# Charging_dock_2_1.net
KiCad netlist of a schematic drawn in EAGLE
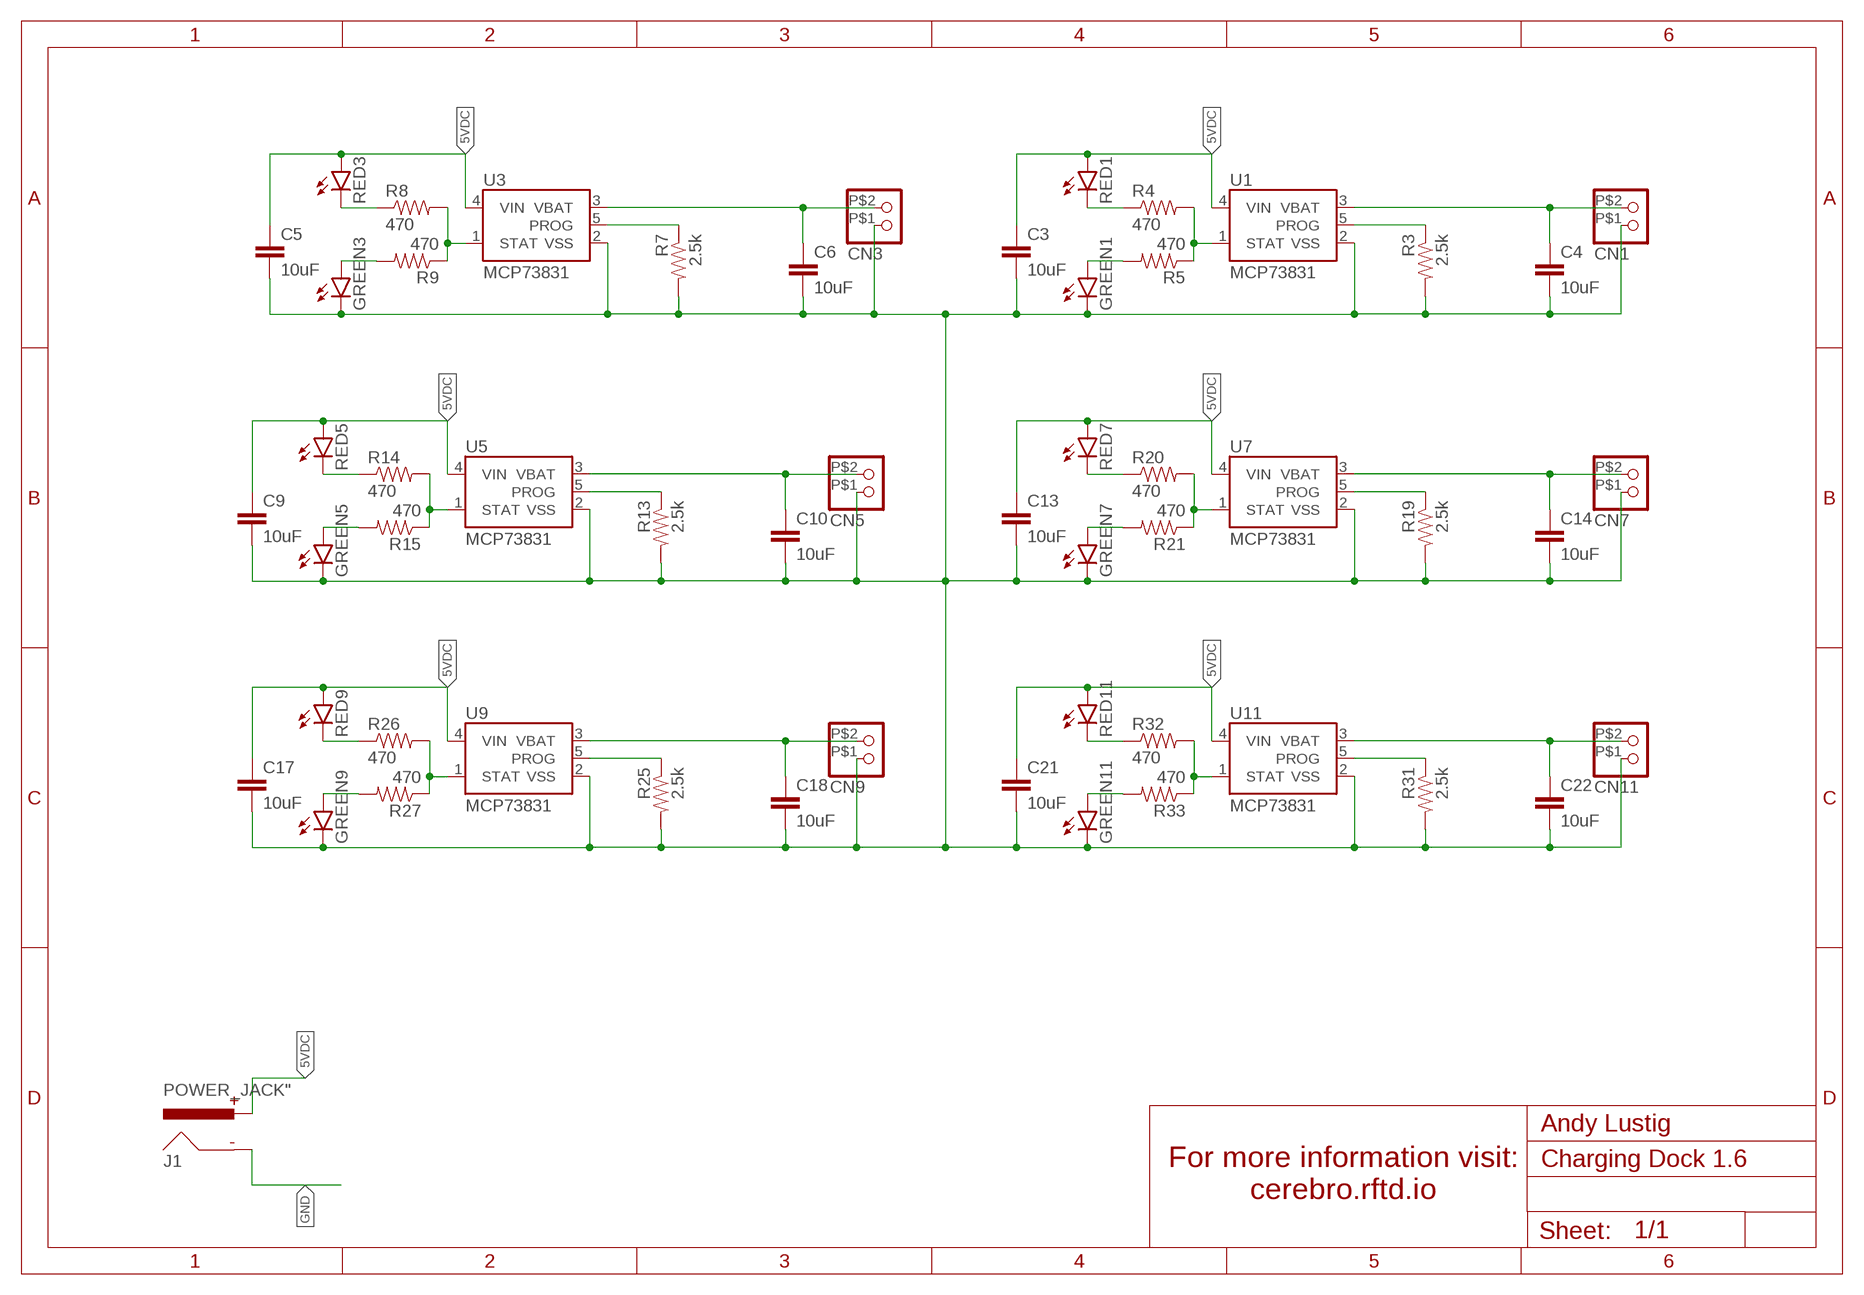
[diagram p0: schematic, sheet 1]

(export (version "E")
  (design (tool "Eeschema 10.0.6"))
  (components
    (comp (ref "C3")
      (value "10uF")
      (footprint "eagle-import:0805")
      (libsource (lib "eagle-import") (part "10UF-0805-10V-10%"))
    )
    (comp (ref "C4")
      (value "10uF")
      (footprint "eagle-import:0805")
      (libsource (lib "eagle-import") (part "10UF-0805-10V-10%"))
    )
    (comp (ref "C5")
      (value "10uF")
      (footprint "eagle-import:0805")
      (libsource (lib "eagle-import") (part "10UF-0805-10V-10%"))
    )
    (comp (ref "C6")
      (value "10uF")
      (footprint "eagle-import:0805")
      (libsource (lib "eagle-import") (part "10UF-0805-10V-10%"))
    )
    (comp (ref "C9")
      (value "10uF")
      (footprint "eagle-import:0805")
      (libsource (lib "eagle-import") (part "10UF-0805-10V-10%"))
    )
    (comp (ref "C10")
      (value "10uF")
      (footprint "eagle-import:0805")
      (libsource (lib "eagle-import") (part "10UF-0805-10V-10%"))
    )
    (comp (ref "C13")
      (value "10uF")
      (footprint "eagle-import:0805")
      (libsource (lib "eagle-import") (part "10UF-0805-10V-10%"))
    )
    (comp (ref "C14")
      (value "10uF")
      (footprint "eagle-import:0805")
      (libsource (lib "eagle-import") (part "10UF-0805-10V-10%"))
    )
    (comp (ref "C17")
      (value "10uF")
      (footprint "eagle-import:0805")
      (libsource (lib "eagle-import") (part "10UF-0805-10V-10%"))
    )
    (comp (ref "C18")
      (value "10uF")
      (footprint "eagle-import:0805")
      (libsource (lib "eagle-import") (part "10UF-0805-10V-10%"))
    )
    (comp (ref "C21")
      (value "10uF")
      (footprint "eagle-import:0805")
      (libsource (lib "eagle-import") (part "10UF-0805-10V-10%"))
    )
    (comp (ref "C22")
      (value "10uF")
      (footprint "eagle-import:0805")
      (libsource (lib "eagle-import") (part "10UF-0805-10V-10%"))
    )
    (comp (ref "CN1")
      (value "JST_2PINMICRO")
      (footprint "eagle-import:MICRO_LOCK_2PIN")
      (libsource (lib "eagle-import") (part "JST_2PINMICRO"))
    )
    (comp (ref "CN3")
      (value "JST_2PINMICRO")
      (footprint "eagle-import:MICRO_LOCK_2PIN")
      (libsource (lib "eagle-import") (part "JST_2PINMICRO"))
    )
    (comp (ref "CN5")
      (value "JST_2PINMICRO")
      (footprint "eagle-import:MICRO_LOCK_2PIN")
      (libsource (lib "eagle-import") (part "JST_2PINMICRO"))
    )
    (comp (ref "CN7")
      (value "JST_2PINMICRO")
      (footprint "eagle-import:MICRO_LOCK_2PIN")
      (libsource (lib "eagle-import") (part "JST_2PINMICRO"))
    )
    (comp (ref "CN9")
      (value "JST_2PINMICRO")
      (footprint "eagle-import:MICRO_LOCK_2PIN")
      (libsource (lib "eagle-import") (part "JST_2PINMICRO"))
    )
    (comp (ref "CN11")
      (value "JST_2PINMICRO")
      (footprint "eagle-import:MICRO_LOCK_2PIN")
      (libsource (lib "eagle-import") (part "JST_2PINMICRO"))
    )
    (comp (ref "GREEN1")
      (value "LED3MM")
      (footprint "eagle-import:LED3MM")
      (libsource (lib "eagle-import") (part "LED3MM"))
    )
    (comp (ref "GREEN3")
      (value "LED3MM")
      (footprint "eagle-import:LED3MM")
      (libsource (lib "eagle-import") (part "LED3MM"))
    )
    (comp (ref "GREEN5")
      (value "LED3MM")
      (footprint "eagle-import:LED3MM")
      (libsource (lib "eagle-import") (part "LED3MM"))
    )
    (comp (ref "GREEN7")
      (value "LED3MM")
      (footprint "eagle-import:LED3MM")
      (libsource (lib "eagle-import") (part "LED3MM"))
    )
    (comp (ref "GREEN9")
      (value "LED3MM")
      (footprint "eagle-import:LED3MM")
      (libsource (lib "eagle-import") (part "LED3MM"))
    )
    (comp (ref "GREEN11")
      (value "LED3MM")
      (footprint "eagle-import:LED3MM")
      (libsource (lib "eagle-import") (part "LED3MM"))
    )
    (comp (ref "J1")
      (value "POWER_JACK\"")
      (footprint "eagle-import:BARREL_CONN")
      (fields (field (name "MANUFACTURER") "CUI Inc"))
      (libsource (lib "eagle-import") (part "POWER_JACK{dblquote}"))
    )
    (comp (ref "R3")
      (value "2.5k")
      (footprint "eagle-import:0805")
      (libsource (lib "eagle-import") (part "RESISTOR0805-RES"))
    )
    (comp (ref "R4")
      (value "470")
      (footprint "eagle-import:0805")
      (libsource (lib "eagle-import") (part "Cerebro-library_RESISTOR0805-RES"))
    )
    (comp (ref "R5")
      (value "470")
      (footprint "eagle-import:0805")
      (libsource (lib "eagle-import") (part "Cerebro-library_RESISTOR0805-RES"))
    )
    (comp (ref "R7")
      (value "2.5k")
      (footprint "eagle-import:0805")
      (libsource (lib "eagle-import") (part "RESISTOR0805-RES"))
    )
    (comp (ref "R8")
      (value "470")
      (footprint "eagle-import:0805")
      (libsource (lib "eagle-import") (part "Cerebro-library_RESISTOR0805-RES"))
    )
    (comp (ref "R9")
      (value "470")
      (footprint "eagle-import:0805")
      (libsource (lib "eagle-import") (part "Cerebro-library_RESISTOR0805-RES"))
    )
    (comp (ref "R13")
      (value "2.5k")
      (footprint "eagle-import:0805")
      (libsource (lib "eagle-import") (part "RESISTOR0805-RES"))
    )
    (comp (ref "R14")
      (value "470")
      (footprint "eagle-import:0805")
      (libsource (lib "eagle-import") (part "Cerebro-library_RESISTOR0805-RES"))
    )
    (comp (ref "R15")
      (value "470")
      (footprint "eagle-import:0805")
      (libsource (lib "eagle-import") (part "Cerebro-library_RESISTOR0805-RES"))
    )
    (comp (ref "R19")
      (value "2.5k")
      (footprint "eagle-import:0805")
      (libsource (lib "eagle-import") (part "RESISTOR0805-RES"))
    )
    (comp (ref "R20")
      (value "470")
      (footprint "eagle-import:0805")
      (libsource (lib "eagle-import") (part "Cerebro-library_RESISTOR0805-RES"))
    )
    (comp (ref "R21")
      (value "470")
      (footprint "eagle-import:0805")
      (libsource (lib "eagle-import") (part "Cerebro-library_RESISTOR0805-RES"))
    )
    (comp (ref "R25")
      (value "2.5k")
      (footprint "eagle-import:0805")
      (libsource (lib "eagle-import") (part "RESISTOR0805-RES"))
    )
    (comp (ref "R26")
      (value "470")
      (footprint "eagle-import:0805")
      (libsource (lib "eagle-import") (part "Cerebro-library_RESISTOR0805-RES"))
    )
    (comp (ref "R27")
      (value "470")
      (footprint "eagle-import:0805")
      (libsource (lib "eagle-import") (part "Cerebro-library_RESISTOR0805-RES"))
    )
    (comp (ref "R31")
      (value "2.5k")
      (footprint "eagle-import:0805")
      (libsource (lib "eagle-import") (part "RESISTOR0805-RES"))
    )
    (comp (ref "R32")
      (value "470")
      (footprint "eagle-import:0805")
      (libsource (lib "eagle-import") (part "Cerebro-library_RESISTOR0805-RES"))
    )
    (comp (ref "R33")
      (value "470")
      (footprint "eagle-import:0805")
      (libsource (lib "eagle-import") (part "Cerebro-library_RESISTOR0805-RES"))
    )
    (comp (ref "RED1")
      (value "LED3MM")
      (footprint "eagle-import:LED3MM")
      (libsource (lib "eagle-import") (part "LED3MM"))
    )
    (comp (ref "RED3")
      (value "LED3MM")
      (footprint "eagle-import:LED3MM")
      (libsource (lib "eagle-import") (part "LED3MM"))
    )
    (comp (ref "RED5")
      (value "LED3MM")
      (footprint "eagle-import:LED3MM")
      (libsource (lib "eagle-import") (part "LED3MM"))
    )
    (comp (ref "RED7")
      (value "LED3MM")
      (footprint "eagle-import:LED3MM")
      (libsource (lib "eagle-import") (part "LED3MM"))
    )
    (comp (ref "RED9")
      (value "LED3MM")
      (footprint "eagle-import:LED3MM")
      (libsource (lib "eagle-import") (part "LED3MM"))
    )
    (comp (ref "RED11")
      (value "LED3MM")
      (footprint "eagle-import:LED3MM")
      (libsource (lib "eagle-import") (part "LED3MM"))
    )
    (comp (ref "U1")
      (value "MCP73831")
      (footprint "eagle-import:SOT23-5")
      (libsource (lib "eagle-import") (part "MCP73831"))
    )
    (comp (ref "U3")
      (value "MCP73831")
      (footprint "eagle-import:SOT23-5")
      (libsource (lib "eagle-import") (part "MCP73831"))
    )
    (comp (ref "U5")
      (value "MCP73831")
      (footprint "eagle-import:SOT23-5")
      (libsource (lib "eagle-import") (part "MCP73831"))
    )
    (comp (ref "U7")
      (value "MCP73831")
      (footprint "eagle-import:SOT23-5")
      (libsource (lib "eagle-import") (part "MCP73831"))
    )
    (comp (ref "U9")
      (value "MCP73831")
      (footprint "eagle-import:SOT23-5")
      (libsource (lib "eagle-import") (part "MCP73831"))
    )
    (comp (ref "U11")
      (value "MCP73831")
      (footprint "eagle-import:SOT23-5")
      (libsource (lib "eagle-import") (part "MCP73831"))
    )
  )
  (nets
    (net (code "1") (name "5VDC") (class "Default")
      (node (ref "C13") (pin "1") (pinfunction "1_1") (pintype "passive"))
      (node (ref "C17") (pin "1") (pinfunction "1_1") (pintype "passive"))
      (node (ref "C21") (pin "1") (pinfunction "1_1") (pintype "passive"))
      (node (ref "C3") (pin "1") (pinfunction "1_1") (pintype "passive"))
      (node (ref "C5") (pin "1") (pinfunction "1_1") (pintype "passive"))
      (node (ref "C9") (pin "1") (pinfunction "1_1") (pintype "passive"))
      (node (ref "J1") (pin "PWR") (pinfunction "PWR_PWR") (pintype "bidirectional"))
      (node (ref "RED1") (pin "A") (pinfunction "A_A") (pintype "passive"))
      (node (ref "RED11") (pin "A") (pinfunction "A_A") (pintype "passive"))
      (node (ref "RED3") (pin "A") (pinfunction "A_A") (pintype "passive"))
      (node (ref "RED5") (pin "A") (pinfunction "A_A") (pintype "passive"))
      (node (ref "RED7") (pin "A") (pinfunction "A_A") (pintype "passive"))
      (node (ref "RED9") (pin "A") (pinfunction "A_A") (pintype "passive"))
      (node (ref "U1") (pin "4") (pinfunction "VIN_4") (pintype "power_in"))
      (node (ref "U11") (pin "4") (pinfunction "VIN_4") (pintype "power_in"))
      (node (ref "U3") (pin "4") (pinfunction "VIN_4") (pintype "power_in"))
      (node (ref "U5") (pin "4") (pinfunction "VIN_4") (pintype "power_in"))
      (node (ref "U7") (pin "4") (pinfunction "VIN_4") (pintype "power_in"))
      (node (ref "U9") (pin "4") (pinfunction "VIN_4") (pintype "power_in"))
    )
    (net (code "2") (name "GND") (class "Default")
      (node (ref "C10") (pin "2") (pinfunction "2_2") (pintype "passive"))
      (node (ref "C13") (pin "2") (pinfunction "2_2") (pintype "passive"))
      (node (ref "C14") (pin "2") (pinfunction "2_2") (pintype "passive"))
      (node (ref "C17") (pin "2") (pinfunction "2_2") (pintype "passive"))
      (node (ref "C18") (pin "2") (pinfunction "2_2") (pintype "passive"))
      (node (ref "C21") (pin "2") (pinfunction "2_2") (pintype "passive"))
      (node (ref "C22") (pin "2") (pinfunction "2_2") (pintype "passive"))
      (node (ref "C3") (pin "2") (pinfunction "2_2") (pintype "passive"))
      (node (ref "C4") (pin "2") (pinfunction "2_2") (pintype "passive"))
      (node (ref "C5") (pin "2") (pinfunction "2_2") (pintype "passive"))
      (node (ref "C6") (pin "2") (pinfunction "2_2") (pintype "passive"))
      (node (ref "C9") (pin "2") (pinfunction "2_2") (pintype "passive"))
      (node (ref "CN1") (pin "P$1") (pinfunction "1_P$1") (pintype "passive"))
      (node (ref "CN11") (pin "P$1") (pinfunction "1_P$1") (pintype "passive"))
      (node (ref "CN3") (pin "P$1") (pinfunction "1_P$1") (pintype "passive"))
      (node (ref "CN5") (pin "P$1") (pinfunction "1_P$1") (pintype "passive"))
      (node (ref "CN7") (pin "P$1") (pinfunction "1_P$1") (pintype "passive"))
      (node (ref "CN9") (pin "P$1") (pinfunction "1_P$1") (pintype "passive"))
      (node (ref "GREEN1") (pin "K") (pinfunction "C_K") (pintype "passive"))
      (node (ref "GREEN11") (pin "K") (pinfunction "C_K") (pintype "passive"))
      (node (ref "GREEN3") (pin "K") (pinfunction "C_K") (pintype "passive"))
      (node (ref "GREEN5") (pin "K") (pinfunction "C_K") (pintype "passive"))
      (node (ref "GREEN7") (pin "K") (pinfunction "C_K") (pintype "passive"))
      (node (ref "GREEN9") (pin "K") (pinfunction "C_K") (pintype "passive"))
      (node (ref "J1") (pin "GND") (pinfunction "GND_GND") (pintype "bidirectional"))
      (node (ref "R13") (pin "2") (pinfunction "2_2") (pintype "passive"))
      (node (ref "R19") (pin "2") (pinfunction "2_2") (pintype "passive"))
      (node (ref "R25") (pin "2") (pinfunction "2_2") (pintype "passive"))
      (node (ref "R3") (pin "2") (pinfunction "2_2") (pintype "passive"))
      (node (ref "R31") (pin "2") (pinfunction "2_2") (pintype "passive"))
      (node (ref "R7") (pin "2") (pinfunction "2_2") (pintype "passive"))
      (node (ref "U1") (pin "2") (pinfunction "VSS_2") (pintype "power_in"))
      (node (ref "U11") (pin "2") (pinfunction "VSS_2") (pintype "power_in"))
      (node (ref "U3") (pin "2") (pinfunction "VSS_2") (pintype "power_in"))
      (node (ref "U5") (pin "2") (pinfunction "VSS_2") (pintype "power_in"))
      (node (ref "U7") (pin "2") (pinfunction "VSS_2") (pintype "power_in"))
      (node (ref "U9") (pin "2") (pinfunction "VSS_2") (pintype "power_in"))
    )
    (net (code "3") (name "Net-(CN1-2)") (class "Default")
      (node (ref "C4") (pin "1") (pinfunction "1_1") (pintype "passive"))
      (node (ref "CN1") (pin "P$2") (pinfunction "2_P$2") (pintype "passive"))
      (node (ref "U1") (pin "3") (pinfunction "VBAT_3") (pintype "power_in"))
    )
    (net (code "4") (name "Net-(CN3-2)") (class "Default")
      (node (ref "C6") (pin "1") (pinfunction "1_1") (pintype "passive"))
      (node (ref "CN3") (pin "P$2") (pinfunction "2_P$2") (pintype "passive"))
      (node (ref "U3") (pin "3") (pinfunction "VBAT_3") (pintype "power_in"))
    )
    (net (code "5") (name "Net-(CN5-2)") (class "Default")
      (node (ref "C10") (pin "1") (pinfunction "1_1") (pintype "passive"))
      (node (ref "CN5") (pin "P$2") (pinfunction "2_P$2") (pintype "passive"))
      (node (ref "U5") (pin "3") (pinfunction "VBAT_3") (pintype "power_in"))
    )
    (net (code "6") (name "Net-(CN7-2)") (class "Default")
      (node (ref "C14") (pin "1") (pinfunction "1_1") (pintype "passive"))
      (node (ref "CN7") (pin "P$2") (pinfunction "2_P$2") (pintype "passive"))
      (node (ref "U7") (pin "3") (pinfunction "VBAT_3") (pintype "power_in"))
    )
    (net (code "7") (name "Net-(CN9-2)") (class "Default")
      (node (ref "C18") (pin "1") (pinfunction "1_1") (pintype "passive"))
      (node (ref "CN9") (pin "P$2") (pinfunction "2_P$2") (pintype "passive"))
      (node (ref "U9") (pin "3") (pinfunction "VBAT_3") (pintype "power_in"))
    )
    (net (code "8") (name "Net-(CN11-2)") (class "Default")
      (node (ref "C22") (pin "1") (pinfunction "1_1") (pintype "passive"))
      (node (ref "CN11") (pin "P$2") (pinfunction "2_P$2") (pintype "passive"))
      (node (ref "U11") (pin "3") (pinfunction "VBAT_3") (pintype "power_in"))
    )
    (net (code "9") (name "Net-(GREEN1-PadA)") (class "Default")
      (node (ref "GREEN1") (pin "A") (pinfunction "A_A") (pintype "passive"))
      (node (ref "R5") (pin "2") (pinfunction "2_2") (pintype "passive"))
    )
    (net (code "10") (name "Net-(GREEN3-PadA)") (class "Default")
      (node (ref "GREEN3") (pin "A") (pinfunction "A_A") (pintype "passive"))
      (node (ref "R9") (pin "2") (pinfunction "2_2") (pintype "passive"))
    )
    (net (code "11") (name "Net-(GREEN5-PadA)") (class "Default")
      (node (ref "GREEN5") (pin "A") (pinfunction "A_A") (pintype "passive"))
      (node (ref "R15") (pin "2") (pinfunction "2_2") (pintype "passive"))
    )
    (net (code "12") (name "Net-(GREEN7-PadA)") (class "Default")
      (node (ref "GREEN7") (pin "A") (pinfunction "A_A") (pintype "passive"))
      (node (ref "R21") (pin "2") (pinfunction "2_2") (pintype "passive"))
    )
    (net (code "13") (name "Net-(GREEN9-PadA)") (class "Default")
      (node (ref "GREEN9") (pin "A") (pinfunction "A_A") (pintype "passive"))
      (node (ref "R27") (pin "2") (pinfunction "2_2") (pintype "passive"))
    )
    (net (code "14") (name "Net-(GREEN11-PadA)") (class "Default")
      (node (ref "GREEN11") (pin "A") (pinfunction "A_A") (pintype "passive"))
      (node (ref "R33") (pin "2") (pinfunction "2_2") (pintype "passive"))
    )
    (net (code "15") (name "Net-(RED1-C)") (class "Default")
      (node (ref "R4") (pin "1") (pinfunction "1_1") (pintype "passive"))
      (node (ref "RED1") (pin "K") (pinfunction "C_K") (pintype "passive"))
    )
    (net (code "16") (name "Net-(RED3-C)") (class "Default")
      (node (ref "R8") (pin "1") (pinfunction "1_1") (pintype "passive"))
      (node (ref "RED3") (pin "K") (pinfunction "C_K") (pintype "passive"))
    )
    (net (code "17") (name "Net-(RED5-C)") (class "Default")
      (node (ref "R14") (pin "1") (pinfunction "1_1") (pintype "passive"))
      (node (ref "RED5") (pin "K") (pinfunction "C_K") (pintype "passive"))
    )
    (net (code "18") (name "Net-(RED7-C)") (class "Default")
      (node (ref "R20") (pin "1") (pinfunction "1_1") (pintype "passive"))
      (node (ref "RED7") (pin "K") (pinfunction "C_K") (pintype "passive"))
    )
    (net (code "19") (name "Net-(RED9-C)") (class "Default")
      (node (ref "R26") (pin "1") (pinfunction "1_1") (pintype "passive"))
      (node (ref "RED9") (pin "K") (pinfunction "C_K") (pintype "passive"))
    )
    (net (code "20") (name "Net-(RED11-C)") (class "Default")
      (node (ref "R32") (pin "1") (pinfunction "1_1") (pintype "passive"))
      (node (ref "RED11") (pin "K") (pinfunction "C_K") (pintype "passive"))
    )
    (net (code "21") (name "Net-(U1-PROG)") (class "Default")
      (node (ref "R3") (pin "1") (pinfunction "1_1") (pintype "passive"))
      (node (ref "U1") (pin "5") (pinfunction "PROG_5") (pintype "input"))
    )
    (net (code "22") (name "Net-(U1-STAT)") (class "Default")
      (node (ref "R4") (pin "2") (pinfunction "2_2") (pintype "passive"))
      (node (ref "R5") (pin "1") (pinfunction "1_1") (pintype "passive"))
      (node (ref "U1") (pin "1") (pinfunction "STAT_1") (pintype "output"))
    )
    (net (code "23") (name "Net-(U3-PROG)") (class "Default")
      (node (ref "R7") (pin "1") (pinfunction "1_1") (pintype "passive"))
      (node (ref "U3") (pin "5") (pinfunction "PROG_5") (pintype "input"))
    )
    (net (code "24") (name "Net-(U3-STAT)") (class "Default")
      (node (ref "R8") (pin "2") (pinfunction "2_2") (pintype "passive"))
      (node (ref "R9") (pin "1") (pinfunction "1_1") (pintype "passive"))
      (node (ref "U3") (pin "1") (pinfunction "STAT_1") (pintype "output"))
    )
    (net (code "25") (name "Net-(U5-PROG)") (class "Default")
      (node (ref "R13") (pin "1") (pinfunction "1_1") (pintype "passive"))
      (node (ref "U5") (pin "5") (pinfunction "PROG_5") (pintype "input"))
    )
    (net (code "26") (name "Net-(U5-STAT)") (class "Default")
      (node (ref "R14") (pin "2") (pinfunction "2_2") (pintype "passive"))
      (node (ref "R15") (pin "1") (pinfunction "1_1") (pintype "passive"))
      (node (ref "U5") (pin "1") (pinfunction "STAT_1") (pintype "output"))
    )
    (net (code "27") (name "Net-(U7-PROG)") (class "Default")
      (node (ref "R19") (pin "1") (pinfunction "1_1") (pintype "passive"))
      (node (ref "U7") (pin "5") (pinfunction "PROG_5") (pintype "input"))
    )
    (net (code "28") (name "Net-(U7-STAT)") (class "Default")
      (node (ref "R20") (pin "2") (pinfunction "2_2") (pintype "passive"))
      (node (ref "R21") (pin "1") (pinfunction "1_1") (pintype "passive"))
      (node (ref "U7") (pin "1") (pinfunction "STAT_1") (pintype "output"))
    )
    (net (code "29") (name "Net-(U9-PROG)") (class "Default")
      (node (ref "R25") (pin "1") (pinfunction "1_1") (pintype "passive"))
      (node (ref "U9") (pin "5") (pinfunction "PROG_5") (pintype "input"))
    )
    (net (code "30") (name "Net-(U9-STAT)") (class "Default")
      (node (ref "R26") (pin "2") (pinfunction "2_2") (pintype "passive"))
      (node (ref "R27") (pin "1") (pinfunction "1_1") (pintype "passive"))
      (node (ref "U9") (pin "1") (pinfunction "STAT_1") (pintype "output"))
    )
    (net (code "31") (name "Net-(U11-PROG)") (class "Default")
      (node (ref "R31") (pin "1") (pinfunction "1_1") (pintype "passive"))
      (node (ref "U11") (pin "5") (pinfunction "PROG_5") (pintype "input"))
    )
    (net (code "32") (name "Net-(U11-STAT)") (class "Default")
      (node (ref "R32") (pin "2") (pinfunction "2_2") (pintype "passive"))
      (node (ref "R33") (pin "1") (pinfunction "1_1") (pintype "passive"))
      (node (ref "U11") (pin "1") (pinfunction "STAT_1") (pintype "output"))
    )
  )
)
